# Alimentation.net
KiCad netlist of a schematic drawn in Altium Designer
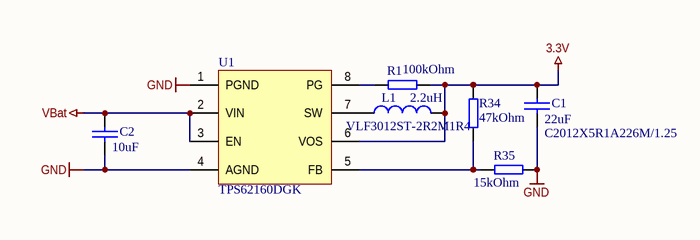
[diagram p0: Alimentation.SchDoc]

(export (version "E")
  (design (tool "Eeschema 10.0.6"))
  (components
    (comp (ref "C1")
      (value "C2012X5R1A226M/1.25")
      (footprint "080501")
      (description "CAPA")
      (fields (field (name "ALTIUM_VALUE") "22uF"))
      (libsource (lib "General-Sch-205") (part "CAPA"))
    )
    (comp (ref "C2")
      (value "10uF")
      (footprint "080501")
      (description "CAPA")
      (fields (field (name "Comment") "GRM21BR61E106KA73L"))
      (libsource (lib "General-Sch-205") (part "CAPA"))
    )
    (comp (ref "L1")
      (value "VLF3012ST-2R2M1R4")
      (footprint "InductanceAlim")
      (fields (field (name "ALTIUM_VALUE") "2.2uH"))
      (libsource (lib "General-Sch-205") (part "INDUCTOR"))
    )
    (comp (ref "R1")
      (value "100kOhm")
      (footprint "080501")
      (fields (field (name "Comment") "ERJ-6GEYJ104V"))
      (libsource (lib "General-Sch-205") (part "RES"))
    )
    (comp (ref "R34")
      (value "47kOhm")
      (footprint "080501")
      (fields (field (name "Comment") "ERJ-6GEYJ104V"))
      (libsource (lib "General-Sch-205") (part "RES"))
    )
    (comp (ref "R35")
      (value "15kOhm")
      (footprint "080501")
      (fields (field (name "Comment") "ERJ-6GEYJ104V"))
      (libsource (lib "General-Sch-205") (part "RES"))
    )
    (comp (ref "U1")
      (value "TPS62160DGK")
      (footprint "TSOP65P490-8AM")
      (description "IC BUCK SYNC ADJ 1A 8MSOP")
      (libsource (lib "Schlib1") (part "TPS62160"))
    )
  )
  (nets
    (net (code "1") (name "3.3V") (class "Default")
      (node (ref "C1") (pin "1") (pintype "passive"))
      (node (ref "L1") (pin "2") (pintype "passive"))
      (node (ref "R1") (pin "2") (pintype "passive"))
      (node (ref "R34") (pin "2") (pintype "passive"))
      (node (ref "U1") (pin "6") (pinfunction "VOS_6") (pintype "passive"))
    )
    (net (code "2") (name "GND") (class "Default")
      (node (ref "C1") (pin "2") (pintype "passive"))
      (node (ref "C2") (pin "2") (pintype "passive"))
      (node (ref "R35") (pin "1") (pintype "passive"))
      (node (ref "U1") (pin "1") (pinfunction "PGND_1") (pintype "passive"))
      (node (ref "U1") (pin "4") (pinfunction "AGND_4") (pintype "passive"))
    )
    (net (code "3") (name "Net-(U1-FB)") (class "Default")
      (node (ref "R34") (pin "1") (pintype "passive"))
      (node (ref "R35") (pin "2") (pintype "passive"))
      (node (ref "U1") (pin "5") (pinfunction "FB_5") (pintype "passive"))
    )
    (net (code "4") (name "Net-(U1-PG)") (class "Default")
      (node (ref "R1") (pin "1") (pintype "passive"))
      (node (ref "U1") (pin "8") (pinfunction "PG_8") (pintype "passive"))
    )
    (net (code "5") (name "Net-(U1-SW)") (class "Default")
      (node (ref "L1") (pin "1") (pintype "passive"))
      (node (ref "U1") (pin "7") (pinfunction "SW_7") (pintype "passive"))
    )
    (net (code "6") (name "VBat") (class "Default")
      (node (ref "C2") (pin "1") (pintype "passive"))
      (node (ref "U1") (pin "2") (pinfunction "VIN_2") (pintype "passive"))
      (node (ref "U1") (pin "3") (pinfunction "EN_3") (pintype "passive"))
    )
  )
)
